# ESP32.net
KiCad netlist of a schematic drawn in Altium Designer
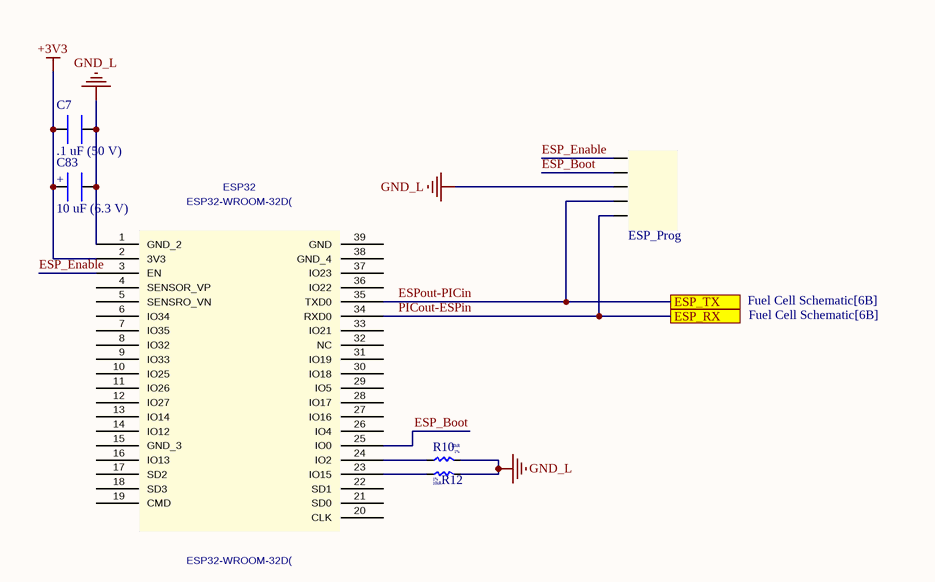
[diagram p0: ESP32.SchDoc]

(export (version "E")
  (design (tool "Eeschema 10.0.6"))
  (components
    (comp (ref "C7")
      (value ".1 uF (50 V)")
      (footprint ".1uF capacitor")
      (libsource (lib "Schlib1") (part ".1 uF cap"))
    )
    (comp (ref "C83")
      (value "10 uF (6.3 V)")
      (footprint "10 uF cap")
      (libsource (lib "Schlib1") (part "10 uF cap"))
    )
    (comp (ref "ESP32")
      (value "ESP32-WROOM-32D(")
      (footprint "ESP32")
      (fields
        (field (name "MANUFACTURER_PART_NUMBER") "ESP32-WROOM-32D(M113DH6400PH3Q0)")
        (field (name "ALTIUM_VALUE") "ESP32-WROOM-32D(")
        (field (name "COPYRIGHT") "Copyright (C) 2023 Ultra Librarian. All rights reserved.")
      )
      (libsource (lib "Schlib1") (part "ESP32-WROOM-32D("))
    )
    (comp (ref "ESP_Prog")
      (value "PIC_ESP_Program")
      (footprint "ESP_PIC_Program")
      (libsource (lib "Schlib1") (part "PIC_ESP_Program"))
    )
    (comp (ref "R10")
      (value "~")
      (footprint "Resistor_YAGEO_0805")
      (description "RES 10K OHM 1% 1/8W 0805")
      (fields
        (field (name "MANUFACTURER") "Yageo")
        (field (name "MANUFACTURER PART NUMBER") "RC0805FR-1010KL")
        (field (name "TOLERANCE") "1%")
        (field (name "RESISTANCE") "10kR")
      )
      (libsource (lib "Schlib1") (part "RC0805FR-1010KL"))
    )
    (comp (ref "R12")
      (value "~")
      (footprint "Resistor_YAGEO_0805")
      (description "RES 10K OHM 1% 1/8W 0805")
      (fields
        (field (name "MANUFACTURER") "Yageo")
        (field (name "MANUFACTURER PART NUMBER") "RC0805FR-1010KL")
        (field (name "TOLERANCE") "1%")
        (field (name "RESISTANCE") "10kR")
      )
      (libsource (lib "Schlib1") (part "RC0805FR-1010KL"))
    )
  )
  (nets
    (net (code "1") (name "+3V3") (class "Default")
      (node (ref "C7") (pin "1") (pinfunction "1_1") (pintype "passive"))
      (node (ref "C83") (pin "1") (pinfunction "1_1") (pintype "passive"))
      (node (ref "ESP32") (pin "2") (pinfunction "3V3_2") (pintype "passive"))
    )
    (net (code "2") (name "/ESP_Boot") (class "Default")
      (node (ref "ESP32") (pin "25") (pinfunction "IO0_25") (pintype "passive"))
      (node (ref "ESP_Prog") (pin "4") (pinfunction "Boot_4") (pintype "passive"))
    )
    (net (code "3") (name "/ESP_Enable") (class "Default")
      (node (ref "ESP32") (pin "3") (pinfunction "EN_3") (pintype "passive"))
      (node (ref "ESP_Prog") (pin "5") (pinfunction "Enable_5") (pintype "passive"))
    )
    (net (code "4") (name "/ESPout-PICin") (class "Default")
      (node (ref "ESP32") (pin "35") (pinfunction "TXD0_35") (pintype "passive"))
      (node (ref "ESP_Prog") (pin "2") (pinfunction "RX_2") (pintype "passive"))
    )
    (net (code "5") (name "/PICout-ESPin") (class "Default")
      (node (ref "ESP32") (pin "34") (pinfunction "RXD0_34") (pintype "passive"))
      (node (ref "ESP_Prog") (pin "1") (pinfunction "TX_1") (pintype "passive"))
    )
    (net (code "6") (name "GND_L") (class "Default")
      (node (ref "C7") (pin "2") (pinfunction "2_2") (pintype "passive"))
      (node (ref "C83") (pin "2") (pinfunction "2_2") (pintype "passive"))
      (node (ref "ESP32") (pin "1") (pinfunction "GND_2_1") (pintype "passive"))
      (node (ref "ESP_Prog") (pin "3") (pinfunction "GND_3") (pintype "passive"))
      (node (ref "R10") (pin "2") (pinfunction "2_2") (pintype "passive"))
      (node (ref "R12") (pin "2") (pinfunction "2_2") (pintype "passive"))
    )
    (net (code "7") (name "Net-(ESP32-IO2)") (class "Default")
      (node (ref "ESP32") (pin "24") (pinfunction "IO2_24") (pintype "passive"))
      (node (ref "R10") (pin "1") (pinfunction "1_1") (pintype "passive"))
    )
    (net (code "8") (name "Net-(ESP32-IO15)") (class "Default")
      (node (ref "ESP32") (pin "23") (pinfunction "IO15_23") (pintype "passive"))
      (node (ref "R12") (pin "1") (pinfunction "1_1") (pintype "passive"))
    )
    (net (code "9") (name "unconnected-(ESP32-CLK-Pad20)") (class "Default")
      (node (ref "ESP32") (pin "20") (pinfunction "CLK_20") (pintype "passive"))
    )
    (net (code "10") (name "unconnected-(ESP32-CMD-Pad19)") (class "Default")
      (node (ref "ESP32") (pin "19") (pinfunction "CMD_19") (pintype "passive"))
    )
    (net (code "11") (name "unconnected-(ESP32-GND-Pad39)") (class "Default")
      (node (ref "ESP32") (pin "39") (pinfunction "GND_39") (pintype "passive"))
    )
    (net (code "12") (name "unconnected-(ESP32-GND_3-Pad15)") (class "Default")
      (node (ref "ESP32") (pin "15") (pinfunction "GND_3_15") (pintype "passive"))
    )
    (net (code "13") (name "unconnected-(ESP32-GND_4-Pad38)") (class "Default")
      (node (ref "ESP32") (pin "38") (pinfunction "GND_4_38") (pintype "passive"))
    )
    (net (code "14") (name "unconnected-(ESP32-IO4-Pad26)") (class "Default")
      (node (ref "ESP32") (pin "26") (pinfunction "IO4_26") (pintype "passive"))
    )
    (net (code "15") (name "unconnected-(ESP32-IO5-Pad29)") (class "Default")
      (node (ref "ESP32") (pin "29") (pinfunction "IO5_29") (pintype "passive"))
    )
    (net (code "16") (name "unconnected-(ESP32-IO12-Pad14)") (class "Default")
      (node (ref "ESP32") (pin "14") (pinfunction "IO12_14") (pintype "passive"))
    )
    (net (code "17") (name "unconnected-(ESP32-IO13-Pad16)") (class "Default")
      (node (ref "ESP32") (pin "16") (pinfunction "IO13_16") (pintype "passive"))
    )
    (net (code "18") (name "unconnected-(ESP32-IO14-Pad13)") (class "Default")
      (node (ref "ESP32") (pin "13") (pinfunction "IO14_13") (pintype "passive"))
    )
    (net (code "19") (name "unconnected-(ESP32-IO16-Pad27)") (class "Default")
      (node (ref "ESP32") (pin "27") (pinfunction "IO16_27") (pintype "passive"))
    )
    (net (code "20") (name "unconnected-(ESP32-IO17-Pad28)") (class "Default")
      (node (ref "ESP32") (pin "28") (pinfunction "IO17_28") (pintype "passive"))
    )
    (net (code "21") (name "unconnected-(ESP32-IO18-Pad30)") (class "Default")
      (node (ref "ESP32") (pin "30") (pinfunction "IO18_30") (pintype "passive"))
    )
    (net (code "22") (name "unconnected-(ESP32-IO19-Pad31)") (class "Default")
      (node (ref "ESP32") (pin "31") (pinfunction "IO19_31") (pintype "passive"))
    )
    (net (code "23") (name "unconnected-(ESP32-IO21-Pad33)") (class "Default")
      (node (ref "ESP32") (pin "33") (pinfunction "IO21_33") (pintype "passive"))
    )
    (net (code "24") (name "unconnected-(ESP32-IO22-Pad36)") (class "Default")
      (node (ref "ESP32") (pin "36") (pinfunction "IO22_36") (pintype "passive"))
    )
    (net (code "25") (name "unconnected-(ESP32-IO23-Pad37)") (class "Default")
      (node (ref "ESP32") (pin "37") (pinfunction "IO23_37") (pintype "passive"))
    )
    (net (code "26") (name "unconnected-(ESP32-IO25-Pad10)") (class "Default")
      (node (ref "ESP32") (pin "10") (pinfunction "IO25_10") (pintype "passive"))
    )
    (net (code "27") (name "unconnected-(ESP32-IO26-Pad11)") (class "Default")
      (node (ref "ESP32") (pin "11") (pinfunction "IO26_11") (pintype "passive"))
    )
    (net (code "28") (name "unconnected-(ESP32-IO27-Pad12)") (class "Default")
      (node (ref "ESP32") (pin "12") (pinfunction "IO27_12") (pintype "passive"))
    )
    (net (code "29") (name "unconnected-(ESP32-IO32-Pad8)") (class "Default")
      (node (ref "ESP32") (pin "8") (pinfunction "IO32_8") (pintype "passive"))
    )
    (net (code "30") (name "unconnected-(ESP32-IO33-Pad9)") (class "Default")
      (node (ref "ESP32") (pin "9") (pinfunction "IO33_9") (pintype "passive"))
    )
    (net (code "31") (name "unconnected-(ESP32-IO34-Pad6)") (class "Default")
      (node (ref "ESP32") (pin "6") (pinfunction "IO34_6") (pintype "passive"))
    )
    (net (code "32") (name "unconnected-(ESP32-IO35-Pad7)") (class "Default")
      (node (ref "ESP32") (pin "7") (pinfunction "IO35_7") (pintype "passive"))
    )
    (net (code "33") (name "unconnected-(ESP32-NC-Pad32)") (class "Default")
      (node (ref "ESP32") (pin "32") (pinfunction "NC_32") (pintype "passive"))
    )
    (net (code "34") (name "unconnected-(ESP32-SD0-Pad21)") (class "Default")
      (node (ref "ESP32") (pin "21") (pinfunction "SD0_21") (pintype "passive"))
    )
    (net (code "35") (name "unconnected-(ESP32-SD1-Pad22)") (class "Default")
      (node (ref "ESP32") (pin "22") (pinfunction "SD1_22") (pintype "passive"))
    )
    (net (code "36") (name "unconnected-(ESP32-SD2-Pad17)") (class "Default")
      (node (ref "ESP32") (pin "17") (pinfunction "SD2_17") (pintype "passive"))
    )
    (net (code "37") (name "unconnected-(ESP32-SD3-Pad18)") (class "Default")
      (node (ref "ESP32") (pin "18") (pinfunction "SD3_18") (pintype "passive"))
    )
    (net (code "38") (name "unconnected-(ESP32-SENSOR_VP-Pad4)") (class "Default")
      (node (ref "ESP32") (pin "4") (pinfunction "SENSOR_VP_4") (pintype "passive"))
    )
    (net (code "39") (name "unconnected-(ESP32-SENSRO_VN-Pad5)") (class "Default")
      (node (ref "ESP32") (pin "5") (pinfunction "SENSRO_VN_5") (pintype "passive"))
    )
  )
)
